# DoorALIM.net
KiCad netlist of a schematic drawn in EAGLE
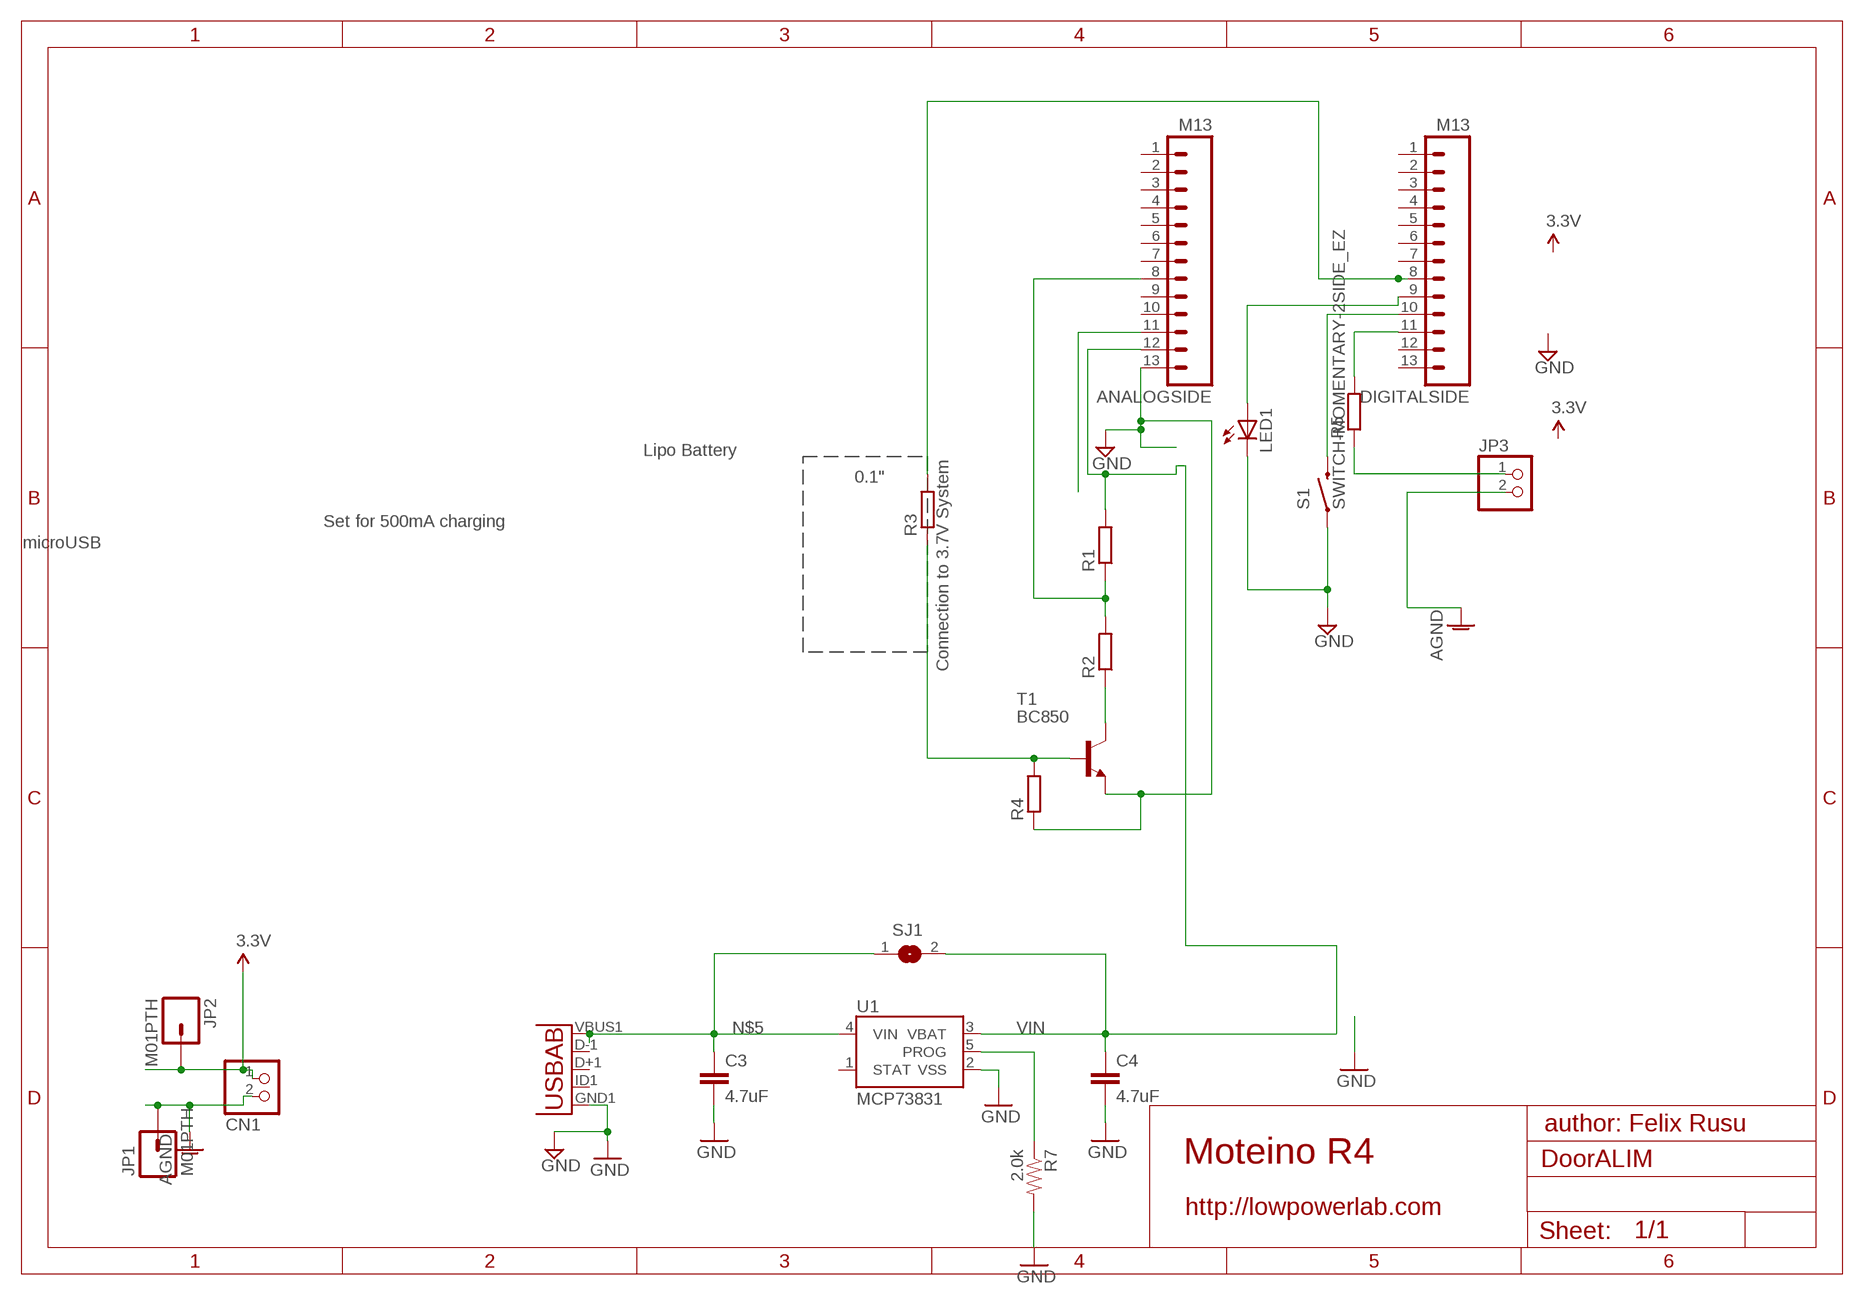
[diagram p0: schematic, sheet 1]

(export (version "E")
  (design (tool "Eeschema 10.0.6"))
  (components
    (comp (ref "ANALOGSIDE")
      (value "M13")
      (footprint "eagle-import:1X13")
      (libsource (lib "eagle-import") (part "M13"))
    )
    (comp (ref "C3")
      (value "4.7uF")
      (footprint "eagle-import:0603-CAP")
      (libsource (lib "eagle-import") (part "4.7UF-6.3V-10%(0603)0603"))
    )
    (comp (ref "C4")
      (value "4.7uF")
      (footprint "eagle-import:0603-CAP")
      (libsource (lib "eagle-import") (part "4.7UF-6.3V-10%(0603)0603"))
    )
    (comp (ref "CN1")
      (value "JST_2PIN-SMT")
      (footprint "eagle-import:JST-PH-2-SMT")
      (libsource (lib "eagle-import") (part "JST_2PIN-SMT"))
    )
    (comp (ref "DIGITALSIDE")
      (value "M13")
      (footprint "eagle-import:1X13")
      (libsource (lib "eagle-import") (part "M13"))
    )
    (comp (ref "JP1")
      (value "M01PTH")
      (footprint "eagle-import:1X01")
      (libsource (lib "eagle-import") (part "M01PTH"))
    )
    (comp (ref "JP2")
      (value "M01PTH")
      (footprint "eagle-import:1X01")
      (libsource (lib "eagle-import") (part "M01PTH"))
    )
    (comp (ref "JP3")
      (value "PINHD-1X2")
      (footprint "eagle-import:1X02")
      (libsource (lib "eagle-import") (part "PINHD-1X2"))
    )
    (comp (ref "JP9")
      (value "Micro USB")
      (footprint "eagle-import:USB-AB-MICRO-SMD_V03")
      (libsource (lib "eagle-import") (part "USB-ABCONN-11794"))
    )
    (comp (ref "LED1")
      (value "LED3MM")
      (footprint "eagle-import:LED3MM")
      (libsource (lib "eagle-import") (part "LED3MM"))
    )
    (comp (ref "R1")
      (value "R-EU_0204/7")
      (footprint "eagle-import:0204_7")
      (libsource (lib "eagle-import") (part "R-EU_0204/7"))
    )
    (comp (ref "R2")
      (value "R-EU_0204/7")
      (footprint "eagle-import:0204_7")
      (libsource (lib "eagle-import") (part "R-EU_0204/7"))
    )
    (comp (ref "R3")
      (value "R-EU_M1206")
      (footprint "eagle-import:M1206")
      (libsource (lib "eagle-import") (part "R-EU_M1206"))
    )
    (comp (ref "R4")
      (value "R-EU_M1206")
      (footprint "eagle-import:M1206")
      (libsource (lib "eagle-import") (part "R-EU_M1206"))
    )
    (comp (ref "R5")
      (value "R-EU_0204/7")
      (footprint "eagle-import:0204_7")
      (libsource (lib "eagle-import") (part "R-EU_0204/7"))
    )
    (comp (ref "R7")
      (value "2.0k")
      (footprint "eagle-import:0603-RES")
      (libsource (lib "eagle-import") (part "2.0KOHM1/10W5%(0603)"))
    )
    (comp (ref "S1")
      (value "SWITCH-MOMENTARY-2SIDE_EZ")
      (footprint "eagle-import:TACTILE-PTH-SIDEEZ")
      (libsource (lib "eagle-import") (part "SWITCH-MOMENTARY-2SIDE_EZ"))
    )
    (comp (ref "SJ1") (value "SJ") (footprint "eagle-import:SJ") (libsource (lib "eagle-import") (part "SJ")))
    (comp (ref "T1")
      (value "BC850")
      (footprint "eagle-import:SOT23")
      (libsource (lib "eagle-import") (part "BC850"))
    )
    (comp (ref "U1")
      (value "MCP73831")
      (footprint "eagle-import:SOT23-5")
      (libsource (lib "eagle-import") (part "MCP73831"))
    )
  )
  (nets
    (net (code "1") (name "/N$5") (class "Default")
      (node (ref "C3") (pin "1") (pinfunction "1_1") (pintype "passive"))
      (node (ref "JP9") (pin "VBUS1") (pinfunction "VBUS_VBUS1") (pintype "bidirectional"))
      (node (ref "SJ1") (pin "1") (pinfunction "1_1") (pintype "passive"))
      (node (ref "U1") (pin "4") (pinfunction "VIN_4") (pintype "power_in"))
    )
    (net (code "2") (name "/VIN") (class "Default")
      (node (ref "ANALOGSIDE") (pin "12") (pinfunction "12_12") (pintype "passive"))
      (node (ref "C4") (pin "1") (pinfunction "1_1") (pintype "passive"))
      (node (ref "R1") (pin "2") (pinfunction "2_2") (pintype "passive"))
      (node (ref "SJ1") (pin "2") (pinfunction "2_2") (pintype "passive"))
      (node (ref "U1") (pin "3") (pinfunction "VBAT_3") (pintype "power_in"))
    )
    (net (code "3") (name "3.3V") (class "Default")
      (node (ref "CN1") (pin "1") (pinfunction "2_1") (pintype "passive"))
      (node (ref "JP2") (pin "1") (pinfunction "1_1") (pintype "passive"))
    )
    (net (code "4") (name "AGND") (class "Default")
      (node (ref "CN1") (pin "2") (pinfunction "1_2") (pintype "passive"))
      (node (ref "JP1") (pin "1") (pinfunction "1_1") (pintype "passive"))
      (node (ref "JP3") (pin "2") (pinfunction "2_2") (pintype "passive"))
    )
    (net (code "5") (name "GND") (class "Default")
      (node (ref "ANALOGSIDE") (pin "13") (pinfunction "13_13") (pintype "passive"))
      (node (ref "C3") (pin "2") (pinfunction "2_2") (pintype "passive"))
      (node (ref "C4") (pin "2") (pinfunction "2_2") (pintype "passive"))
      (node (ref "JP9") (pin "GND1") (pinfunction "GND_GND1") (pintype "bidirectional"))
      (node (ref "LED1") (pin "K") (pinfunction "C_K") (pintype "passive"))
      (node (ref "R4") (pin "1") (pinfunction "1_1") (pintype "passive"))
      (node (ref "R7") (pin "2") (pinfunction "2_2") (pintype "passive"))
      (node (ref "S1") (pin "1") (pinfunction "1_1") (pintype "passive"))
      (node (ref "T1") (pin "2") (pinfunction "E_2") (pintype "passive"))
      (node (ref "U1") (pin "2") (pinfunction "VSS_2") (pintype "power_in"))
    )
    (net (code "6") (name "Net-(ANALOGSIDE-Pad8)") (class "Default")
      (node (ref "ANALOGSIDE") (pin "8") (pinfunction "8_8") (pintype "passive"))
      (node (ref "R1") (pin "1") (pinfunction "1_1") (pintype "passive"))
      (node (ref "R2") (pin "2") (pinfunction "2_2") (pintype "passive"))
    )
    (net (code "7") (name "Net-(DIGITALSIDE-Pad8)") (class "Default")
      (node (ref "DIGITALSIDE") (pin "8") (pinfunction "8_8") (pintype "passive"))
      (node (ref "R3") (pin "2") (pinfunction "2_2") (pintype "passive"))
    )
    (net (code "8") (name "Net-(DIGITALSIDE-Pad9)") (class "Default")
      (node (ref "DIGITALSIDE") (pin "9") (pinfunction "9_9") (pintype "passive"))
      (node (ref "LED1") (pin "A") (pinfunction "A_A") (pintype "passive"))
    )
    (net (code "9") (name "Net-(DIGITALSIDE-Pad10)") (class "Default")
      (node (ref "DIGITALSIDE") (pin "10") (pinfunction "10_10") (pintype "passive"))
      (node (ref "S1") (pin "2") (pinfunction "2_2") (pintype "passive"))
    )
    (net (code "10") (name "Net-(DIGITALSIDE-Pad11)") (class "Default")
      (node (ref "DIGITALSIDE") (pin "11") (pinfunction "11_11") (pintype "passive"))
      (node (ref "R5") (pin "2") (pinfunction "2_2") (pintype "passive"))
    )
    (net (code "11") (name "Net-(JP3-Pad1)") (class "Default")
      (node (ref "JP3") (pin "1") (pinfunction "1_1") (pintype "passive"))
      (node (ref "R5") (pin "1") (pinfunction "1_1") (pintype "passive"))
    )
    (net (code "12") (name "Net-(T1-B)") (class "Default")
      (node (ref "R3") (pin "1") (pinfunction "1_1") (pintype "passive"))
      (node (ref "R4") (pin "2") (pinfunction "2_2") (pintype "passive"))
      (node (ref "T1") (pin "1") (pinfunction "B_1") (pintype "passive"))
    )
    (net (code "13") (name "Net-(T1-C)") (class "Default")
      (node (ref "R2") (pin "1") (pinfunction "1_1") (pintype "passive"))
      (node (ref "T1") (pin "3") (pinfunction "C_3") (pintype "passive"))
    )
    (net (code "14") (name "Net-(U1-PROG)") (class "Default")
      (node (ref "R7") (pin "1") (pinfunction "1_1") (pintype "passive"))
      (node (ref "U1") (pin "5") (pinfunction "PROG_5") (pintype "input"))
    )
    (net (code "15") (name "unconnected-(ANALOGSIDE-Pad1)") (class "Default")
      (node (ref "ANALOGSIDE") (pin "1") (pinfunction "1_1") (pintype "passive"))
    )
    (net (code "16") (name "unconnected-(ANALOGSIDE-Pad2)") (class "Default")
      (node (ref "ANALOGSIDE") (pin "2") (pinfunction "2_2") (pintype "passive"))
    )
    (net (code "17") (name "unconnected-(ANALOGSIDE-Pad3)") (class "Default")
      (node (ref "ANALOGSIDE") (pin "3") (pinfunction "3_3") (pintype "passive"))
    )
    (net (code "18") (name "unconnected-(ANALOGSIDE-Pad4)") (class "Default")
      (node (ref "ANALOGSIDE") (pin "4") (pinfunction "4_4") (pintype "passive"))
    )
    (net (code "19") (name "unconnected-(ANALOGSIDE-Pad5)") (class "Default")
      (node (ref "ANALOGSIDE") (pin "5") (pinfunction "5_5") (pintype "passive"))
    )
    (net (code "20") (name "unconnected-(ANALOGSIDE-Pad6)") (class "Default")
      (node (ref "ANALOGSIDE") (pin "6") (pinfunction "6_6") (pintype "passive"))
    )
    (net (code "21") (name "unconnected-(ANALOGSIDE-Pad7)") (class "Default")
      (node (ref "ANALOGSIDE") (pin "7") (pinfunction "7_7") (pintype "passive"))
    )
    (net (code "22") (name "unconnected-(ANALOGSIDE-Pad9)") (class "Default")
      (node (ref "ANALOGSIDE") (pin "9") (pinfunction "9_9") (pintype "passive"))
    )
    (net (code "23") (name "unconnected-(ANALOGSIDE-Pad10)") (class "Default")
      (node (ref "ANALOGSIDE") (pin "10") (pinfunction "10_10") (pintype "passive"))
    )
    (net (code "24") (name "unconnected-(ANALOGSIDE-Pad11)") (class "Default")
      (node (ref "ANALOGSIDE") (pin "11") (pinfunction "11_11") (pintype "passive"))
    )
    (net (code "25") (name "unconnected-(DIGITALSIDE-Pad1)") (class "Default")
      (node (ref "DIGITALSIDE") (pin "1") (pinfunction "1_1") (pintype "passive"))
    )
    (net (code "26") (name "unconnected-(DIGITALSIDE-Pad2)") (class "Default")
      (node (ref "DIGITALSIDE") (pin "2") (pinfunction "2_2") (pintype "passive"))
    )
    (net (code "27") (name "unconnected-(DIGITALSIDE-Pad3)") (class "Default")
      (node (ref "DIGITALSIDE") (pin "3") (pinfunction "3_3") (pintype "passive"))
    )
    (net (code "28") (name "unconnected-(DIGITALSIDE-Pad4)") (class "Default")
      (node (ref "DIGITALSIDE") (pin "4") (pinfunction "4_4") (pintype "passive"))
    )
    (net (code "29") (name "unconnected-(DIGITALSIDE-Pad5)") (class "Default")
      (node (ref "DIGITALSIDE") (pin "5") (pinfunction "5_5") (pintype "passive"))
    )
    (net (code "30") (name "unconnected-(DIGITALSIDE-Pad6)") (class "Default")
      (node (ref "DIGITALSIDE") (pin "6") (pinfunction "6_6") (pintype "passive"))
    )
    (net (code "31") (name "unconnected-(DIGITALSIDE-Pad7)") (class "Default")
      (node (ref "DIGITALSIDE") (pin "7") (pinfunction "7_7") (pintype "passive"))
    )
    (net (code "32") (name "unconnected-(DIGITALSIDE-Pad12)") (class "Default")
      (node (ref "DIGITALSIDE") (pin "12") (pinfunction "12_12") (pintype "passive"))
    )
    (net (code "33") (name "unconnected-(DIGITALSIDE-Pad13)") (class "Default")
      (node (ref "DIGITALSIDE") (pin "13") (pinfunction "13_13") (pintype "passive"))
    )
    (net (code "34") (name "unconnected-(JP9-D+-PadD+1)") (class "Default")
      (node (ref "JP9") (pin "D+1") (pinfunction "D+_D+1") (pintype "bidirectional"))
    )
    (net (code "35") (name "unconnected-(JP9-D--PadD-1)") (class "Default")
      (node (ref "JP9") (pin "D-1") (pinfunction "D-_D-1") (pintype "bidirectional"))
    )
    (net (code "36") (name "unconnected-(JP9-USBID-PadID1)") (class "Default")
      (node (ref "JP9") (pin "ID1") (pinfunction "USBID_ID1") (pintype "bidirectional"))
    )
    (net (code "37") (name "unconnected-(U1-STAT-Pad1)") (class "Default")
      (node (ref "U1") (pin "1") (pinfunction "STAT_1") (pintype "output"))
    )
  )
)
